# FrantPannel.net
KiCad netlist of a schematic drawn in Altium Designer
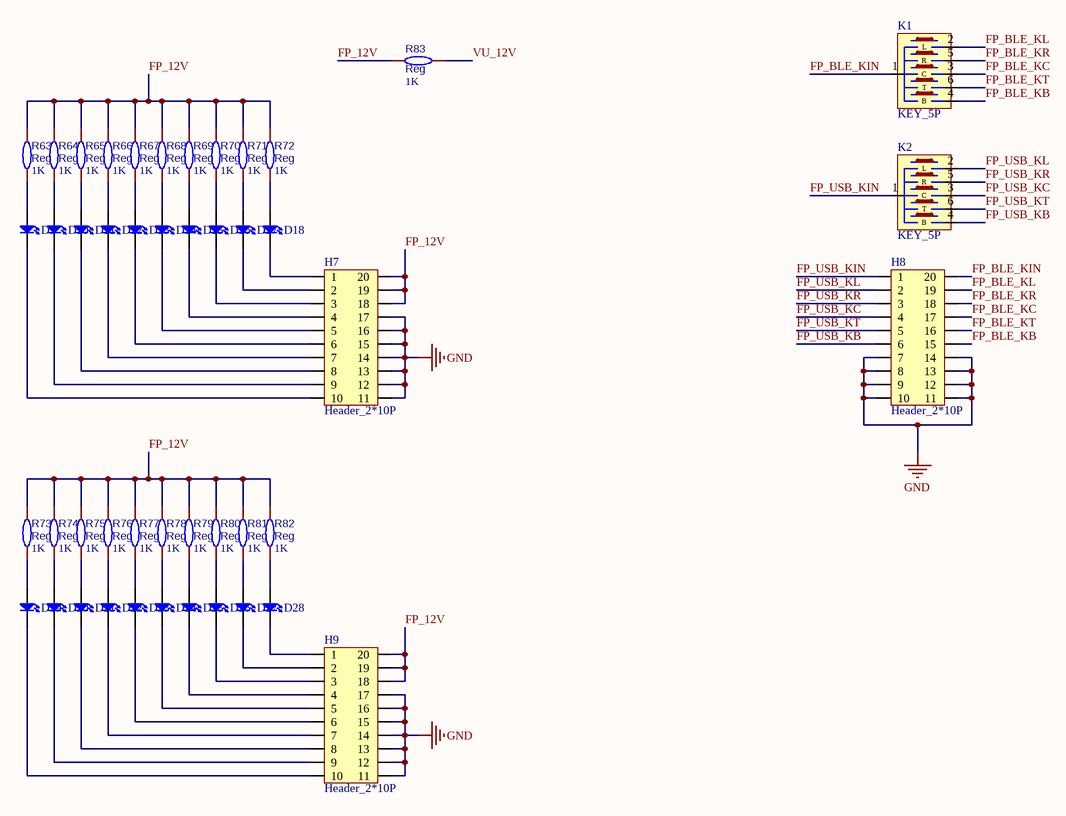
[diagram p0: FrantPannel.SchDoc]

(export (version "E")
  (design (tool "Eeschema 10.0.6"))
  (components
    (comp (ref "D9")
      (value "LED")
      (footprint "LED0603")
      (fields (field (name "PUBLISHER") "Altium Limited"))
      (libsource (lib "Levent_lib") (part "LED0"))
    )
    (comp (ref "D10")
      (value "LED")
      (footprint "LED0603")
      (fields (field (name "PUBLISHER") "Altium Limited"))
      (libsource (lib "Levent_lib") (part "LED0"))
    )
    (comp (ref "D11")
      (value "LED")
      (footprint "LED0603")
      (fields (field (name "PUBLISHER") "Altium Limited"))
      (libsource (lib "Levent_lib") (part "LED0"))
    )
    (comp (ref "D12")
      (value "LED")
      (footprint "LED0603")
      (fields (field (name "PUBLISHER") "Altium Limited"))
      (libsource (lib "Levent_lib") (part "LED0"))
    )
    (comp (ref "D13")
      (value "LED")
      (footprint "LED0603")
      (fields (field (name "PUBLISHER") "Altium Limited"))
      (libsource (lib "Levent_lib") (part "LED0"))
    )
    (comp (ref "D14")
      (value "LED")
      (footprint "LED0603")
      (fields (field (name "PUBLISHER") "Altium Limited"))
      (libsource (lib "Levent_lib") (part "LED0"))
    )
    (comp (ref "D15")
      (value "LED")
      (footprint "LED0603")
      (fields (field (name "PUBLISHER") "Altium Limited"))
      (libsource (lib "Levent_lib") (part "LED0"))
    )
    (comp (ref "D16")
      (value "LED")
      (footprint "LED0603")
      (fields (field (name "PUBLISHER") "Altium Limited"))
      (libsource (lib "Levent_lib") (part "LED0"))
    )
    (comp (ref "D17")
      (value "LED")
      (footprint "LED0603")
      (fields (field (name "PUBLISHER") "Altium Limited"))
      (libsource (lib "Levent_lib") (part "LED0"))
    )
    (comp (ref "D18")
      (value "LED")
      (footprint "LED0603")
      (fields (field (name "PUBLISHER") "Altium Limited"))
      (libsource (lib "Levent_lib") (part "LED0"))
    )
    (comp (ref "D19")
      (value "LED")
      (footprint "LED0603")
      (fields (field (name "PUBLISHER") "Altium Limited"))
      (libsource (lib "Levent_lib") (part "LED0"))
    )
    (comp (ref "D20")
      (value "LED")
      (footprint "LED0603")
      (fields (field (name "PUBLISHER") "Altium Limited"))
      (libsource (lib "Levent_lib") (part "LED0"))
    )
    (comp (ref "D21")
      (value "LED")
      (footprint "LED0603")
      (fields (field (name "PUBLISHER") "Altium Limited"))
      (libsource (lib "Levent_lib") (part "LED0"))
    )
    (comp (ref "D22")
      (value "LED")
      (footprint "LED0603")
      (fields (field (name "PUBLISHER") "Altium Limited"))
      (libsource (lib "Levent_lib") (part "LED0"))
    )
    (comp (ref "D23")
      (value "LED")
      (footprint "LED0603")
      (fields (field (name "PUBLISHER") "Altium Limited"))
      (libsource (lib "Levent_lib") (part "LED0"))
    )
    (comp (ref "D24")
      (value "LED")
      (footprint "LED0603")
      (fields (field (name "PUBLISHER") "Altium Limited"))
      (libsource (lib "Levent_lib") (part "LED0"))
    )
    (comp (ref "D25")
      (value "LED")
      (footprint "LED0603")
      (fields (field (name "PUBLISHER") "Altium Limited"))
      (libsource (lib "Levent_lib") (part "LED0"))
    )
    (comp (ref "D26")
      (value "LED")
      (footprint "LED0603")
      (fields (field (name "PUBLISHER") "Altium Limited"))
      (libsource (lib "Levent_lib") (part "LED0"))
    )
    (comp (ref "D27")
      (value "LED")
      (footprint "LED0603")
      (fields (field (name "PUBLISHER") "Altium Limited"))
      (libsource (lib "Levent_lib") (part "LED0"))
    )
    (comp (ref "D28")
      (value "LED")
      (footprint "LED0603")
      (fields (field (name "PUBLISHER") "Altium Limited"))
      (libsource (lib "Levent_lib") (part "LED0"))
    )
    (comp (ref "H7")
      (value "Header_2*10P")
      (footprint "H_2.0_2x10Pin_SMD")
      (description "2*10P连接器")
      (libsource (lib "Levent_lib") (part "Header_2*10P"))
    )
    (comp (ref "H8")
      (value "Header_2*10P")
      (footprint "H_2.0_2x10Pin_SMD")
      (description "2*10P连接器")
      (libsource (lib "Levent_lib") (part "Header_2*10P"))
    )
    (comp (ref "H9")
      (value "Header_2*10P")
      (footprint "H_2.0_2x10Pin_SMD")
      (description "2*10P连接器")
      (libsource (lib "Levent_lib") (part "Header_2*10P"))
    )
    (comp (ref "K1")
      (value "KEY_5P")
      (footprint "KEY_5")
      (description "五向开关")
      (libsource (lib "Levent_lib") (part "KEY_5P"))
    )
    (comp (ref "K2")
      (value "KEY_5P")
      (footprint "KEY_5")
      (description "五向开关")
      (libsource (lib "Levent_lib") (part "KEY_5P"))
    )
    (comp (ref "R63")
      (value "Reg")
      (footprint "R0603")
      (description "电阻")
      (fields
        (field (name "BOM_SUPPLIER PART") "C465721")
        (field (name "BOM_MANUFACTURER PART") "AR03BTCX1002A")
        (field (name "ALTIUM_VALUE") "1K")
        (field (name "CONTRIBUTOR") "LCSC")
      )
      (libsource (lib "Levent_lib") (part "Res"))
    )
    (comp (ref "R64")
      (value "Reg")
      (footprint "R0603")
      (description "电阻")
      (fields
        (field (name "BOM_SUPPLIER PART") "C465721")
        (field (name "BOM_MANUFACTURER PART") "AR03BTCX1002A")
        (field (name "ALTIUM_VALUE") "1K")
        (field (name "CONTRIBUTOR") "LCSC")
      )
      (libsource (lib "Levent_lib") (part "Res"))
    )
    (comp (ref "R65")
      (value "Reg")
      (footprint "R0603")
      (description "电阻")
      (fields
        (field (name "BOM_SUPPLIER PART") "C465721")
        (field (name "BOM_MANUFACTURER PART") "AR03BTCX1002A")
        (field (name "ALTIUM_VALUE") "1K")
        (field (name "CONTRIBUTOR") "LCSC")
      )
      (libsource (lib "Levent_lib") (part "Res"))
    )
    (comp (ref "R66")
      (value "Reg")
      (footprint "R0603")
      (description "电阻")
      (fields
        (field (name "BOM_SUPPLIER PART") "C465721")
        (field (name "BOM_MANUFACTURER PART") "AR03BTCX1002A")
        (field (name "ALTIUM_VALUE") "1K")
        (field (name "CONTRIBUTOR") "LCSC")
      )
      (libsource (lib "Levent_lib") (part "Res"))
    )
    (comp (ref "R67")
      (value "Reg")
      (footprint "R0603")
      (description "电阻")
      (fields
        (field (name "BOM_SUPPLIER PART") "C465721")
        (field (name "BOM_MANUFACTURER PART") "AR03BTCX1002A")
        (field (name "ALTIUM_VALUE") "1K")
        (field (name "CONTRIBUTOR") "LCSC")
      )
      (libsource (lib "Levent_lib") (part "Res"))
    )
    (comp (ref "R68")
      (value "Reg")
      (footprint "R0603")
      (description "电阻")
      (fields
        (field (name "BOM_SUPPLIER PART") "C465721")
        (field (name "BOM_MANUFACTURER PART") "AR03BTCX1002A")
        (field (name "ALTIUM_VALUE") "1K")
        (field (name "CONTRIBUTOR") "LCSC")
      )
      (libsource (lib "Levent_lib") (part "Res"))
    )
    (comp (ref "R69")
      (value "Reg")
      (footprint "R0603")
      (description "电阻")
      (fields
        (field (name "BOM_SUPPLIER PART") "C465721")
        (field (name "BOM_MANUFACTURER PART") "AR03BTCX1002A")
        (field (name "ALTIUM_VALUE") "1K")
        (field (name "CONTRIBUTOR") "LCSC")
      )
      (libsource (lib "Levent_lib") (part "Res"))
    )
    (comp (ref "R70")
      (value "Reg")
      (footprint "R0603")
      (description "电阻")
      (fields
        (field (name "BOM_SUPPLIER PART") "C465721")
        (field (name "BOM_MANUFACTURER PART") "AR03BTCX1002A")
        (field (name "ALTIUM_VALUE") "1K")
        (field (name "CONTRIBUTOR") "LCSC")
      )
      (libsource (lib "Levent_lib") (part "Res"))
    )
    (comp (ref "R71")
      (value "Reg")
      (footprint "R0603")
      (description "电阻")
      (fields
        (field (name "BOM_SUPPLIER PART") "C465721")
        (field (name "BOM_MANUFACTURER PART") "AR03BTCX1002A")
        (field (name "ALTIUM_VALUE") "1K")
        (field (name "CONTRIBUTOR") "LCSC")
      )
      (libsource (lib "Levent_lib") (part "Res"))
    )
    (comp (ref "R72")
      (value "Reg")
      (footprint "R0603")
      (description "电阻")
      (fields
        (field (name "BOM_SUPPLIER PART") "C465721")
        (field (name "BOM_MANUFACTURER PART") "AR03BTCX1002A")
        (field (name "ALTIUM_VALUE") "1K")
        (field (name "CONTRIBUTOR") "LCSC")
      )
      (libsource (lib "Levent_lib") (part "Res"))
    )
    (comp (ref "R73")
      (value "Reg")
      (footprint "R0603")
      (description "电阻")
      (fields
        (field (name "BOM_SUPPLIER PART") "C465721")
        (field (name "BOM_MANUFACTURER PART") "AR03BTCX1002A")
        (field (name "ALTIUM_VALUE") "1K")
        (field (name "CONTRIBUTOR") "LCSC")
      )
      (libsource (lib "Levent_lib") (part "Res"))
    )
    (comp (ref "R74")
      (value "Reg")
      (footprint "R0603")
      (description "电阻")
      (fields
        (field (name "BOM_SUPPLIER PART") "C465721")
        (field (name "BOM_MANUFACTURER PART") "AR03BTCX1002A")
        (field (name "ALTIUM_VALUE") "1K")
        (field (name "CONTRIBUTOR") "LCSC")
      )
      (libsource (lib "Levent_lib") (part "Res"))
    )
    (comp (ref "R75")
      (value "Reg")
      (footprint "R0603")
      (description "电阻")
      (fields
        (field (name "BOM_SUPPLIER PART") "C465721")
        (field (name "BOM_MANUFACTURER PART") "AR03BTCX1002A")
        (field (name "ALTIUM_VALUE") "1K")
        (field (name "CONTRIBUTOR") "LCSC")
      )
      (libsource (lib "Levent_lib") (part "Res"))
    )
    (comp (ref "R76")
      (value "Reg")
      (footprint "R0603")
      (description "电阻")
      (fields
        (field (name "BOM_SUPPLIER PART") "C465721")
        (field (name "BOM_MANUFACTURER PART") "AR03BTCX1002A")
        (field (name "ALTIUM_VALUE") "1K")
        (field (name "CONTRIBUTOR") "LCSC")
      )
      (libsource (lib "Levent_lib") (part "Res"))
    )
    (comp (ref "R77")
      (value "Reg")
      (footprint "R0603")
      (description "电阻")
      (fields
        (field (name "BOM_SUPPLIER PART") "C465721")
        (field (name "BOM_MANUFACTURER PART") "AR03BTCX1002A")
        (field (name "ALTIUM_VALUE") "1K")
        (field (name "CONTRIBUTOR") "LCSC")
      )
      (libsource (lib "Levent_lib") (part "Res"))
    )
    (comp (ref "R78")
      (value "Reg")
      (footprint "R0603")
      (description "电阻")
      (fields
        (field (name "BOM_SUPPLIER PART") "C465721")
        (field (name "BOM_MANUFACTURER PART") "AR03BTCX1002A")
        (field (name "ALTIUM_VALUE") "1K")
        (field (name "CONTRIBUTOR") "LCSC")
      )
      (libsource (lib "Levent_lib") (part "Res"))
    )
    (comp (ref "R79")
      (value "Reg")
      (footprint "R0603")
      (description "电阻")
      (fields
        (field (name "BOM_SUPPLIER PART") "C465721")
        (field (name "BOM_MANUFACTURER PART") "AR03BTCX1002A")
        (field (name "ALTIUM_VALUE") "1K")
        (field (name "CONTRIBUTOR") "LCSC")
      )
      (libsource (lib "Levent_lib") (part "Res"))
    )
    (comp (ref "R80")
      (value "Reg")
      (footprint "R0603")
      (description "电阻")
      (fields
        (field (name "BOM_SUPPLIER PART") "C465721")
        (field (name "BOM_MANUFACTURER PART") "AR03BTCX1002A")
        (field (name "ALTIUM_VALUE") "1K")
        (field (name "CONTRIBUTOR") "LCSC")
      )
      (libsource (lib "Levent_lib") (part "Res"))
    )
    (comp (ref "R81")
      (value "Reg")
      (footprint "R0603")
      (description "电阻")
      (fields
        (field (name "BOM_SUPPLIER PART") "C465721")
        (field (name "BOM_MANUFACTURER PART") "AR03BTCX1002A")
        (field (name "ALTIUM_VALUE") "1K")
        (field (name "CONTRIBUTOR") "LCSC")
      )
      (libsource (lib "Levent_lib") (part "Res"))
    )
    (comp (ref "R82")
      (value "Reg")
      (footprint "R0603")
      (description "电阻")
      (fields
        (field (name "BOM_SUPPLIER PART") "C465721")
        (field (name "BOM_MANUFACTURER PART") "AR03BTCX1002A")
        (field (name "ALTIUM_VALUE") "1K")
        (field (name "CONTRIBUTOR") "LCSC")
      )
      (libsource (lib "Levent_lib") (part "Res"))
    )
    (comp (ref "R83")
      (value "Reg")
      (footprint "R0603")
      (description "电阻")
      (fields
        (field (name "BOM_SUPPLIER PART") "C465721")
        (field (name "BOM_MANUFACTURER PART") "AR03BTCX1002A")
        (field (name "ALTIUM_VALUE") "1K")
        (field (name "CONTRIBUTOR") "LCSC")
      )
      (libsource (lib "Levent_lib") (part "Res"))
    )
  )
  (nets
    (net (code "1") (name "/FP_12V") (class "Default")
      (node (ref "H7") (pin "18") (pinfunction "18_18") (pintype "passive"))
      (node (ref "H7") (pin "19") (pinfunction "19_19") (pintype "passive"))
      (node (ref "H7") (pin "20") (pinfunction "20_20") (pintype "passive"))
      (node (ref "H9") (pin "18") (pinfunction "18_18") (pintype "passive"))
      (node (ref "H9") (pin "19") (pinfunction "19_19") (pintype "passive"))
      (node (ref "H9") (pin "20") (pinfunction "20_20") (pintype "passive"))
      (node (ref "R63") (pin "2") (pinfunction "2_2") (pintype "passive"))
      (node (ref "R64") (pin "2") (pinfunction "2_2") (pintype "passive"))
      (node (ref "R65") (pin "2") (pinfunction "2_2") (pintype "passive"))
      (node (ref "R66") (pin "2") (pinfunction "2_2") (pintype "passive"))
      (node (ref "R67") (pin "2") (pinfunction "2_2") (pintype "passive"))
      (node (ref "R68") (pin "2") (pinfunction "2_2") (pintype "passive"))
      (node (ref "R69") (pin "2") (pinfunction "2_2") (pintype "passive"))
      (node (ref "R70") (pin "2") (pinfunction "2_2") (pintype "passive"))
      (node (ref "R71") (pin "2") (pinfunction "2_2") (pintype "passive"))
      (node (ref "R72") (pin "2") (pinfunction "2_2") (pintype "passive"))
      (node (ref "R73") (pin "2") (pinfunction "2_2") (pintype "passive"))
      (node (ref "R74") (pin "2") (pinfunction "2_2") (pintype "passive"))
      (node (ref "R75") (pin "2") (pinfunction "2_2") (pintype "passive"))
      (node (ref "R76") (pin "2") (pinfunction "2_2") (pintype "passive"))
      (node (ref "R77") (pin "2") (pinfunction "2_2") (pintype "passive"))
      (node (ref "R78") (pin "2") (pinfunction "2_2") (pintype "passive"))
      (node (ref "R79") (pin "2") (pinfunction "2_2") (pintype "passive"))
      (node (ref "R80") (pin "2") (pinfunction "2_2") (pintype "passive"))
      (node (ref "R81") (pin "2") (pinfunction "2_2") (pintype "passive"))
      (node (ref "R82") (pin "2") (pinfunction "2_2") (pintype "passive"))
      (node (ref "R83") (pin "2") (pinfunction "2_2") (pintype "passive"))
    )
    (net (code "2") (name "/FP_BLE_KB") (class "Default")
      (node (ref "H8") (pin "15") (pinfunction "15_15") (pintype "passive"))
      (node (ref "K1") (pin "4") (pinfunction "B_4") (pintype "passive"))
    )
    (net (code "3") (name "/FP_BLE_KC") (class "Default")
      (node (ref "H8") (pin "17") (pinfunction "17_17") (pintype "passive"))
      (node (ref "K1") (pin "3") (pinfunction "C_3") (pintype "passive"))
    )
    (net (code "4") (name "/FP_BLE_KIN") (class "Default")
      (node (ref "H8") (pin "20") (pinfunction "20_20") (pintype "passive"))
      (node (ref "K1") (pin "1") (pinfunction "G_1") (pintype "passive"))
    )
    (net (code "5") (name "/FP_BLE_KL") (class "Default")
      (node (ref "H8") (pin "19") (pinfunction "19_19") (pintype "passive"))
      (node (ref "K1") (pin "2") (pinfunction "L_2") (pintype "passive"))
    )
    (net (code "6") (name "/FP_BLE_KR") (class "Default")
      (node (ref "H8") (pin "18") (pinfunction "18_18") (pintype "passive"))
      (node (ref "K1") (pin "5") (pinfunction "R_5") (pintype "passive"))
    )
    (net (code "7") (name "/FP_BLE_KT") (class "Default")
      (node (ref "H8") (pin "16") (pinfunction "16_16") (pintype "passive"))
      (node (ref "K1") (pin "6") (pinfunction "T_6") (pintype "passive"))
    )
    (net (code "8") (name "/FP_USB_KB") (class "Default")
      (node (ref "H8") (pin "6") (pinfunction "6_6") (pintype "passive"))
      (node (ref "K2") (pin "4") (pinfunction "B_4") (pintype "passive"))
    )
    (net (code "9") (name "/FP_USB_KC") (class "Default")
      (node (ref "H8") (pin "4") (pinfunction "4_4") (pintype "passive"))
      (node (ref "K2") (pin "3") (pinfunction "C_3") (pintype "passive"))
    )
    (net (code "10") (name "/FP_USB_KIN") (class "Default")
      (node (ref "H8") (pin "1") (pinfunction "1_1") (pintype "passive"))
      (node (ref "K2") (pin "1") (pinfunction "G_1") (pintype "passive"))
    )
    (net (code "11") (name "/FP_USB_KL") (class "Default")
      (node (ref "H8") (pin "2") (pinfunction "2_2") (pintype "passive"))
      (node (ref "K2") (pin "2") (pinfunction "L_2") (pintype "passive"))
    )
    (net (code "12") (name "/FP_USB_KR") (class "Default")
      (node (ref "H8") (pin "3") (pinfunction "3_3") (pintype "passive"))
      (node (ref "K2") (pin "5") (pinfunction "R_5") (pintype "passive"))
    )
    (net (code "13") (name "/FP_USB_KT") (class "Default")
      (node (ref "H8") (pin "5") (pinfunction "5_5") (pintype "passive"))
      (node (ref "K2") (pin "6") (pinfunction "T_6") (pintype "passive"))
    )
    (net (code "14") (name "/VU_12V") (class "Default")
      (node (ref "R83") (pin "1") (pinfunction "1_1") (pintype "passive"))
    )
    (net (code "15") (name "GND") (class "Default")
      (node (ref "H7") (pin "11") (pinfunction "11_11") (pintype "passive"))
      (node (ref "H7") (pin "12") (pinfunction "12_12") (pintype "passive"))
      (node (ref "H7") (pin "13") (pinfunction "13_13") (pintype "passive"))
      (node (ref "H7") (pin "14") (pinfunction "14_14") (pintype "passive"))
      (node (ref "H7") (pin "15") (pinfunction "15_15") (pintype "passive"))
      (node (ref "H7") (pin "16") (pinfunction "16_16") (pintype "passive"))
      (node (ref "H7") (pin "17") (pinfunction "17_17") (pintype "passive"))
      (node (ref "H8") (pin "10") (pinfunction "10_10") (pintype "passive"))
      (node (ref "H8") (pin "11") (pinfunction "11_11") (pintype "passive"))
      (node (ref "H8") (pin "12") (pinfunction "12_12") (pintype "passive"))
      (node (ref "H8") (pin "13") (pinfunction "13_13") (pintype "passive"))
      (node (ref "H8") (pin "14") (pinfunction "14_14") (pintype "passive"))
      (node (ref "H8") (pin "7") (pinfunction "7_7") (pintype "passive"))
      (node (ref "H8") (pin "8") (pinfunction "8_8") (pintype "passive"))
      (node (ref "H8") (pin "9") (pinfunction "9_9") (pintype "passive"))
      (node (ref "H9") (pin "11") (pinfunction "11_11") (pintype "passive"))
      (node (ref "H9") (pin "12") (pinfunction "12_12") (pintype "passive"))
      (node (ref "H9") (pin "13") (pinfunction "13_13") (pintype "passive"))
      (node (ref "H9") (pin "14") (pinfunction "14_14") (pintype "passive"))
      (node (ref "H9") (pin "15") (pinfunction "15_15") (pintype "passive"))
      (node (ref "H9") (pin "16") (pinfunction "16_16") (pintype "passive"))
      (node (ref "H9") (pin "17") (pinfunction "17_17") (pintype "passive"))
    )
    (net (code "16") (name "Net-(D9-A)") (class "Default")
      (node (ref "D9") (pin "2") (pinfunction "A_2") (pintype "passive"))
      (node (ref "R63") (pin "1") (pinfunction "1_1") (pintype "passive"))
    )
    (net (code "17") (name "Net-(D9-K)") (class "Default")
      (node (ref "D9") (pin "1") (pinfunction "K_1") (pintype "passive"))
      (node (ref "H7") (pin "10") (pinfunction "10_10") (pintype "passive"))
    )
    (net (code "18") (name "Net-(D10-A)") (class "Default")
      (node (ref "D10") (pin "2") (pinfunction "A_2") (pintype "passive"))
      (node (ref "R64") (pin "1") (pinfunction "1_1") (pintype "passive"))
    )
    (net (code "19") (name "Net-(D10-K)") (class "Default")
      (node (ref "D10") (pin "1") (pinfunction "K_1") (pintype "passive"))
      (node (ref "H7") (pin "9") (pinfunction "9_9") (pintype "passive"))
    )
    (net (code "20") (name "Net-(D11-A)") (class "Default")
      (node (ref "D11") (pin "2") (pinfunction "A_2") (pintype "passive"))
      (node (ref "R65") (pin "1") (pinfunction "1_1") (pintype "passive"))
    )
    (net (code "21") (name "Net-(D11-K)") (class "Default")
      (node (ref "D11") (pin "1") (pinfunction "K_1") (pintype "passive"))
      (node (ref "H7") (pin "8") (pinfunction "8_8") (pintype "passive"))
    )
    (net (code "22") (name "Net-(D12-A)") (class "Default")
      (node (ref "D12") (pin "2") (pinfunction "A_2") (pintype "passive"))
      (node (ref "R66") (pin "1") (pinfunction "1_1") (pintype "passive"))
    )
    (net (code "23") (name "Net-(D12-K)") (class "Default")
      (node (ref "D12") (pin "1") (pinfunction "K_1") (pintype "passive"))
      (node (ref "H7") (pin "7") (pinfunction "7_7") (pintype "passive"))
    )
    (net (code "24") (name "Net-(D13-A)") (class "Default")
      (node (ref "D13") (pin "2") (pinfunction "A_2") (pintype "passive"))
      (node (ref "R67") (pin "1") (pinfunction "1_1") (pintype "passive"))
    )
    (net (code "25") (name "Net-(D13-K)") (class "Default")
      (node (ref "D13") (pin "1") (pinfunction "K_1") (pintype "passive"))
      (node (ref "H7") (pin "6") (pinfunction "6_6") (pintype "passive"))
    )
    (net (code "26") (name "Net-(D14-A)") (class "Default")
      (node (ref "D14") (pin "2") (pinfunction "A_2") (pintype "passive"))
      (node (ref "R68") (pin "1") (pinfunction "1_1") (pintype "passive"))
    )
    (net (code "27") (name "Net-(D14-K)") (class "Default")
      (node (ref "D14") (pin "1") (pinfunction "K_1") (pintype "passive"))
      (node (ref "H7") (pin "5") (pinfunction "5_5") (pintype "passive"))
    )
    (net (code "28") (name "Net-(D15-A)") (class "Default")
      (node (ref "D15") (pin "2") (pinfunction "A_2") (pintype "passive"))
      (node (ref "R69") (pin "1") (pinfunction "1_1") (pintype "passive"))
    )
    (net (code "29") (name "Net-(D15-K)") (class "Default")
      (node (ref "D15") (pin "1") (pinfunction "K_1") (pintype "passive"))
      (node (ref "H7") (pin "4") (pinfunction "4_4") (pintype "passive"))
    )
    (net (code "30") (name "Net-(D16-A)") (class "Default")
      (node (ref "D16") (pin "2") (pinfunction "A_2") (pintype "passive"))
      (node (ref "R70") (pin "1") (pinfunction "1_1") (pintype "passive"))
    )
    (net (code "31") (name "Net-(D16-K)") (class "Default")
      (node (ref "D16") (pin "1") (pinfunction "K_1") (pintype "passive"))
      (node (ref "H7") (pin "3") (pinfunction "3_3") (pintype "passive"))
    )
    (net (code "32") (name "Net-(D17-A)") (class "Default")
      (node (ref "D17") (pin "2") (pinfunction "A_2") (pintype "passive"))
      (node (ref "R71") (pin "1") (pinfunction "1_1") (pintype "passive"))
    )
    (net (code "33") (name "Net-(D17-K)") (class "Default")
      (node (ref "D17") (pin "1") (pinfunction "K_1") (pintype "passive"))
      (node (ref "H7") (pin "2") (pinfunction "2_2") (pintype "passive"))
    )
    (net (code "34") (name "Net-(D18-A)") (class "Default")
      (node (ref "D18") (pin "2") (pinfunction "A_2") (pintype "passive"))
      (node (ref "R72") (pin "1") (pinfunction "1_1") (pintype "passive"))
    )
    (net (code "35") (name "Net-(D18-K)") (class "Default")
      (node (ref "D18") (pin "1") (pinfunction "K_1") (pintype "passive"))
      (node (ref "H7") (pin "1") (pinfunction "1_1") (pintype "passive"))
    )
    (net (code "36") (name "Net-(D19-A)") (class "Default")
      (node (ref "D19") (pin "2") (pinfunction "A_2") (pintype "passive"))
      (node (ref "R73") (pin "1") (pinfunction "1_1") (pintype "passive"))
    )
    (net (code "37") (name "Net-(D19-K)") (class "Default")
      (node (ref "D19") (pin "1") (pinfunction "K_1") (pintype "passive"))
      (node (ref "H9") (pin "10") (pinfunction "10_10") (pintype "passive"))
    )
    (net (code "38") (name "Net-(D20-A)") (class "Default")
      (node (ref "D20") (pin "2") (pinfunction "A_2") (pintype "passive"))
      (node (ref "R74") (pin "1") (pinfunction "1_1") (pintype "passive"))
    )
    (net (code "39") (name "Net-(D20-K)") (class "Default")
      (node (ref "D20") (pin "1") (pinfunction "K_1") (pintype "passive"))
      (node (ref "H9") (pin "9") (pinfunction "9_9") (pintype "passive"))
    )
    (net (code "40") (name "Net-(D21-A)") (class "Default")
      (node (ref "D21") (pin "2") (pinfunction "A_2") (pintype "passive"))
      (node (ref "R75") (pin "1") (pinfunction "1_1") (pintype "passive"))
    )
    (net (code "41") (name "Net-(D21-K)") (class "Default")
      (node (ref "D21") (pin "1") (pinfunction "K_1") (pintype "passive"))
      (node (ref "H9") (pin "8") (pinfunction "8_8") (pintype "passive"))
    )
    (net (code "42") (name "Net-(D22-A)") (class "Default")
      (node (ref "D22") (pin "2") (pinfunction "A_2") (pintype "passive"))
      (node (ref "R76") (pin "1") (pinfunction "1_1") (pintype "passive"))
    )
    (net (code "43") (name "Net-(D22-K)") (class "Default")
      (node (ref "D22") (pin "1") (pinfunction "K_1") (pintype "passive"))
      (node (ref "H9") (pin "7") (pinfunction "7_7") (pintype "passive"))
    )
    (net (code "44") (name "Net-(D23-A)") (class "Default")
      (node (ref "D23") (pin "2") (pinfunction "A_2") (pintype "passive"))
      (node (ref "R77") (pin "1") (pinfunction "1_1") (pintype "passive"))
    )
    (net (code "45") (name "Net-(D23-K)") (class "Default")
      (node (ref "D23") (pin "1") (pinfunction "K_1") (pintype "passive"))
      (node (ref "H9") (pin "6") (pinfunction "6_6") (pintype "passive"))
    )
    (net (code "46") (name "Net-(D24-A)") (class "Default")
      (node (ref "D24") (pin "2") (pinfunction "A_2") (pintype "passive"))
      (node (ref "R78") (pin "1") (pinfunction "1_1") (pintype "passive"))
    )
    (net (code "47") (name "Net-(D24-K)") (class "Default")
      (node (ref "D24") (pin "1") (pinfunction "K_1") (pintype "passive"))
      (node (ref "H9") (pin "5") (pinfunction "5_5") (pintype "passive"))
    )
    (net (code "48") (name "Net-(D25-A)") (class "Default")
      (node (ref "D25") (pin "2") (pinfunction "A_2") (pintype "passive"))
      (node (ref "R79") (pin "1") (pinfunction "1_1") (pintype "passive"))
    )
    (net (code "49") (name "Net-(D25-K)") (class "Default")
      (node (ref "D25") (pin "1") (pinfunction "K_1") (pintype "passive"))
      (node (ref "H9") (pin "4") (pinfunction "4_4") (pintype "passive"))
    )
    (net (code "50") (name "Net-(D26-A)") (class "Default")
      (node (ref "D26") (pin "2") (pinfunction "A_2") (pintype "passive"))
      (node (ref "R80") (pin "1") (pinfunction "1_1") (pintype "passive"))
    )
    (net (code "51") (name "Net-(D26-K)") (class "Default")
      (node (ref "D26") (pin "1") (pinfunction "K_1") (pintype "passive"))
      (node (ref "H9") (pin "3") (pinfunction "3_3") (pintype "passive"))
    )
    (net (code "52") (name "Net-(D27-A)") (class "Default")
      (node (ref "D27") (pin "2") (pinfunction "A_2") (pintype "passive"))
      (node (ref "R81") (pin "1") (pinfunction "1_1") (pintype "passive"))
    )
    (net (code "53") (name "Net-(D27-K)") (class "Default")
      (node (ref "D27") (pin "1") (pinfunction "K_1") (pintype "passive"))
      (node (ref "H9") (pin "2") (pinfunction "2_2") (pintype "passive"))
    )
    (net (code "54") (name "Net-(D28-A)") (class "Default")
      (node (ref "D28") (pin "2") (pinfunction "A_2") (pintype "passive"))
      (node (ref "R82") (pin "1") (pinfunction "1_1") (pintype "passive"))
    )
    (net (code "55") (name "Net-(D28-K)") (class "Default")
      (node (ref "D28") (pin "1") (pinfunction "K_1") (pintype "passive"))
      (node (ref "H9") (pin "1") (pinfunction "1_1") (pintype "passive"))
    )
  )
)
